# DBG-002.net
KiCad netlist of a schematic drawn in EAGLE
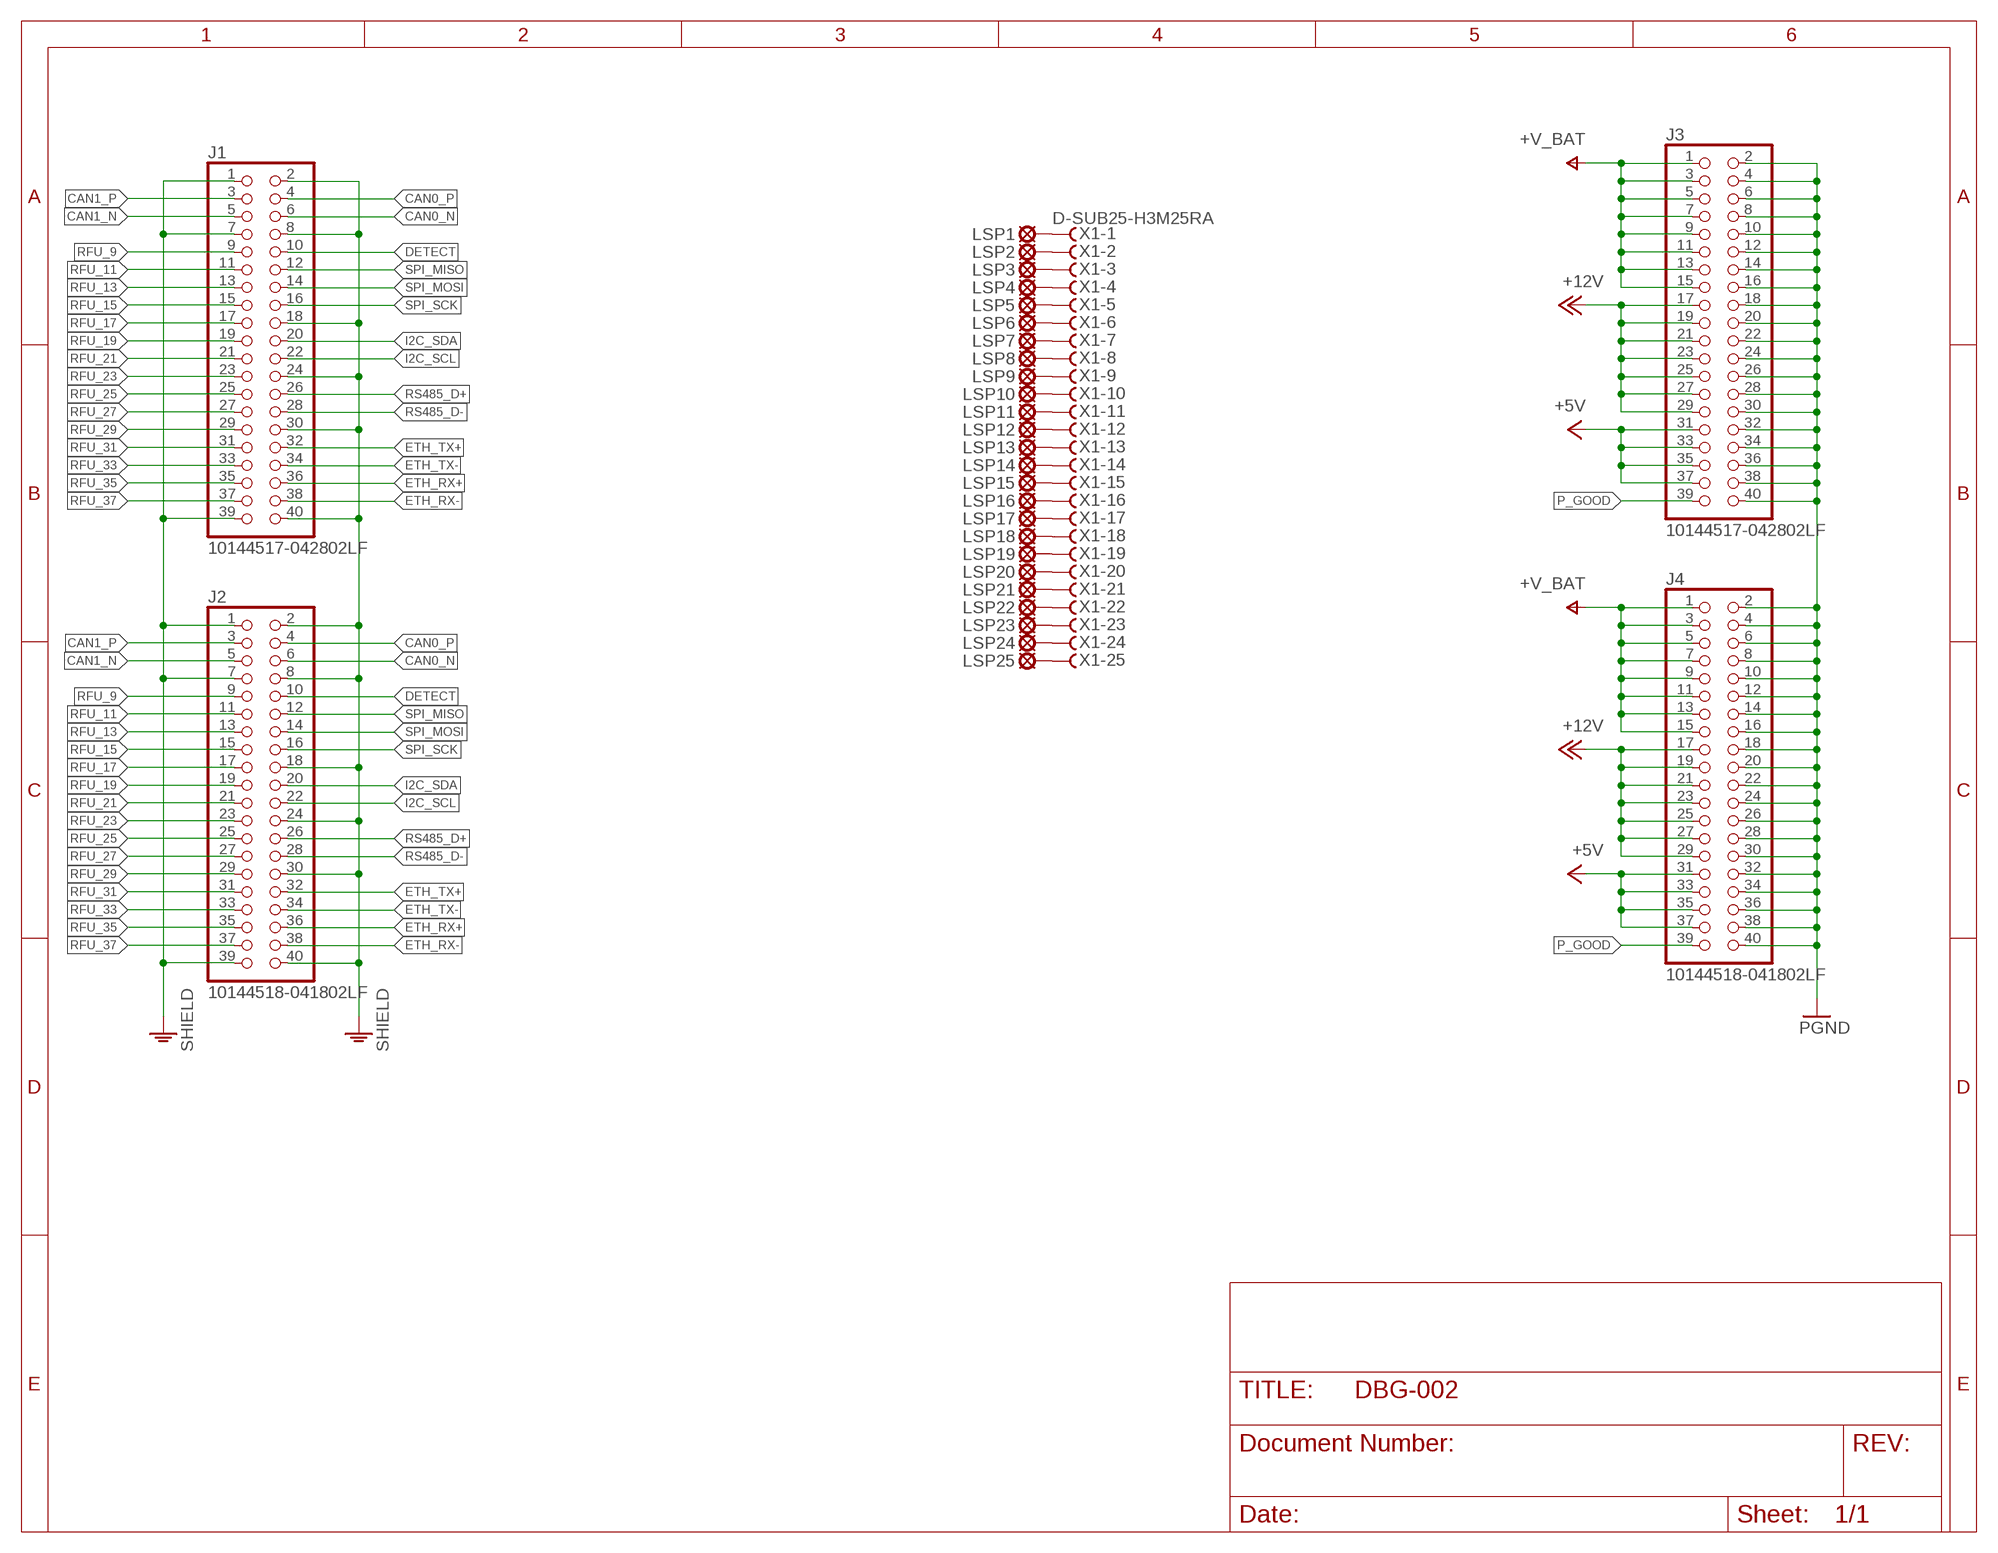
[diagram p0: schematic, sheet 1]

(export (version "E")
  (design (tool "Eeschema 10.0.6"))
  (components
    (comp (ref "J1")
      (value "10144517-042802LF")
      (footprint "eagle-import:10144517-042802LF")
      (libsource (lib "eagle-import") (part "10144517-042802LF"))
    )
    (comp (ref "J2")
      (value "10144518-041802LF")
      (footprint "eagle-import:10144518-041802LF")
      (libsource (lib "eagle-import") (part "10144518-041802LF"))
    )
    (comp (ref "J3")
      (value "10144517-042802LF")
      (footprint "eagle-import:10144517-042802LF")
      (libsource (lib "eagle-import") (part "10144517-042802LF"))
    )
    (comp (ref "J4")
      (value "10144518-041802LF")
      (footprint "eagle-import:10144518-041802LF")
      (libsource (lib "eagle-import") (part "10144518-041802LF"))
    )
    (comp (ref "LSP1")
      (value "LSP11")
      (footprint "eagle-import:LSP11")
      (libsource (lib "eagle-import") (part "LSP11"))
    )
    (comp (ref "LSP2")
      (value "LSP11")
      (footprint "eagle-import:LSP11")
      (libsource (lib "eagle-import") (part "LSP11"))
    )
    (comp (ref "LSP3")
      (value "LSP11")
      (footprint "eagle-import:LSP11")
      (libsource (lib "eagle-import") (part "LSP11"))
    )
    (comp (ref "LSP4")
      (value "LSP11")
      (footprint "eagle-import:LSP11")
      (libsource (lib "eagle-import") (part "LSP11"))
    )
    (comp (ref "LSP5")
      (value "LSP11")
      (footprint "eagle-import:LSP11")
      (libsource (lib "eagle-import") (part "LSP11"))
    )
    (comp (ref "LSP6")
      (value "LSP11")
      (footprint "eagle-import:LSP11")
      (libsource (lib "eagle-import") (part "LSP11"))
    )
    (comp (ref "LSP7")
      (value "LSP11")
      (footprint "eagle-import:LSP11")
      (libsource (lib "eagle-import") (part "LSP11"))
    )
    (comp (ref "LSP8")
      (value "LSP11")
      (footprint "eagle-import:LSP11")
      (libsource (lib "eagle-import") (part "LSP11"))
    )
    (comp (ref "LSP9")
      (value "LSP11")
      (footprint "eagle-import:LSP11")
      (libsource (lib "eagle-import") (part "LSP11"))
    )
    (comp (ref "LSP10")
      (value "LSP11")
      (footprint "eagle-import:LSP11")
      (libsource (lib "eagle-import") (part "LSP11"))
    )
    (comp (ref "LSP11")
      (value "LSP11")
      (footprint "eagle-import:LSP11")
      (libsource (lib "eagle-import") (part "LSP11"))
    )
    (comp (ref "LSP12")
      (value "LSP11")
      (footprint "eagle-import:LSP11")
      (libsource (lib "eagle-import") (part "LSP11"))
    )
    (comp (ref "LSP13")
      (value "LSP11")
      (footprint "eagle-import:LSP11")
      (libsource (lib "eagle-import") (part "LSP11"))
    )
    (comp (ref "LSP14")
      (value "LSP11")
      (footprint "eagle-import:LSP11")
      (libsource (lib "eagle-import") (part "LSP11"))
    )
    (comp (ref "LSP15")
      (value "LSP11")
      (footprint "eagle-import:LSP11")
      (libsource (lib "eagle-import") (part "LSP11"))
    )
    (comp (ref "LSP16")
      (value "LSP11")
      (footprint "eagle-import:LSP11")
      (libsource (lib "eagle-import") (part "LSP11"))
    )
    (comp (ref "LSP17")
      (value "LSP11")
      (footprint "eagle-import:LSP11")
      (libsource (lib "eagle-import") (part "LSP11"))
    )
    (comp (ref "LSP18")
      (value "LSP11")
      (footprint "eagle-import:LSP11")
      (libsource (lib "eagle-import") (part "LSP11"))
    )
    (comp (ref "LSP19")
      (value "LSP11")
      (footprint "eagle-import:LSP11")
      (libsource (lib "eagle-import") (part "LSP11"))
    )
    (comp (ref "LSP20")
      (value "LSP11")
      (footprint "eagle-import:LSP11")
      (libsource (lib "eagle-import") (part "LSP11"))
    )
    (comp (ref "LSP21")
      (value "LSP11")
      (footprint "eagle-import:LSP11")
      (libsource (lib "eagle-import") (part "LSP11"))
    )
    (comp (ref "LSP22")
      (value "LSP11")
      (footprint "eagle-import:LSP11")
      (libsource (lib "eagle-import") (part "LSP11"))
    )
    (comp (ref "LSP23")
      (value "LSP11")
      (footprint "eagle-import:LSP11")
      (libsource (lib "eagle-import") (part "LSP11"))
    )
    (comp (ref "LSP24")
      (value "LSP11")
      (footprint "eagle-import:LSP11")
      (libsource (lib "eagle-import") (part "LSP11"))
    )
    (comp (ref "LSP25")
      (value "LSP11")
      (footprint "eagle-import:LSP11")
      (libsource (lib "eagle-import") (part "LSP11"))
    )
    (comp (ref "X1")
      (value "D-SUB25-H3M25RA")
      (footprint "eagle-import:H3M25RA")
      (libsource (lib "eagle-import") (part "D-SUB25-H3M25RA"))
    )
  )
  (nets
    (net (code "1") (name "+5V") (class "Default")
      (node (ref "J3") (pin "31") (pinfunction "31_31") (pintype "passive"))
      (node (ref "J3") (pin "33") (pinfunction "33_33") (pintype "passive"))
      (node (ref "J3") (pin "35") (pinfunction "35_35") (pintype "passive"))
      (node (ref "J3") (pin "37") (pinfunction "37_37") (pintype "passive"))
      (node (ref "J4") (pin "31") (pinfunction "31_31") (pintype "passive"))
      (node (ref "J4") (pin "33") (pinfunction "33_33") (pintype "passive"))
      (node (ref "J4") (pin "35") (pinfunction "35_35") (pintype "passive"))
      (node (ref "J4") (pin "37") (pinfunction "37_37") (pintype "passive"))
    )
    (net (code "2") (name "+12V") (class "Default")
      (node (ref "J3") (pin "17") (pinfunction "17_17") (pintype "passive"))
      (node (ref "J3") (pin "19") (pinfunction "19_19") (pintype "passive"))
      (node (ref "J3") (pin "21") (pinfunction "21_21") (pintype "passive"))
      (node (ref "J3") (pin "23") (pinfunction "23_23") (pintype "passive"))
      (node (ref "J3") (pin "25") (pinfunction "25_25") (pintype "passive"))
      (node (ref "J3") (pin "27") (pinfunction "27_27") (pintype "passive"))
      (node (ref "J3") (pin "29") (pinfunction "29_29") (pintype "passive"))
      (node (ref "J4") (pin "17") (pinfunction "17_17") (pintype "passive"))
      (node (ref "J4") (pin "19") (pinfunction "19_19") (pintype "passive"))
      (node (ref "J4") (pin "21") (pinfunction "21_21") (pintype "passive"))
      (node (ref "J4") (pin "23") (pinfunction "23_23") (pintype "passive"))
      (node (ref "J4") (pin "25") (pinfunction "25_25") (pintype "passive"))
      (node (ref "J4") (pin "27") (pinfunction "27_27") (pintype "passive"))
      (node (ref "J4") (pin "29") (pinfunction "29_29") (pintype "passive"))
    )
    (net (code "3") (name "+V_BAT") (class "Default")
      (node (ref "J3") (pin "1") (pinfunction "1_1") (pintype "passive"))
      (node (ref "J3") (pin "11") (pinfunction "11_11") (pintype "passive"))
      (node (ref "J3") (pin "13") (pinfunction "13_13") (pintype "passive"))
      (node (ref "J3") (pin "15") (pinfunction "15_15") (pintype "passive"))
      (node (ref "J3") (pin "3") (pinfunction "3_3") (pintype "passive"))
      (node (ref "J3") (pin "5") (pinfunction "5_5") (pintype "passive"))
      (node (ref "J3") (pin "7") (pinfunction "7_7") (pintype "passive"))
      (node (ref "J3") (pin "9") (pinfunction "9_9") (pintype "passive"))
      (node (ref "J4") (pin "1") (pinfunction "1_1") (pintype "passive"))
      (node (ref "J4") (pin "11") (pinfunction "11_11") (pintype "passive"))
      (node (ref "J4") (pin "13") (pinfunction "13_13") (pintype "passive"))
      (node (ref "J4") (pin "15") (pinfunction "15_15") (pintype "passive"))
      (node (ref "J4") (pin "3") (pinfunction "3_3") (pintype "passive"))
      (node (ref "J4") (pin "5") (pinfunction "5_5") (pintype "passive"))
      (node (ref "J4") (pin "7") (pinfunction "7_7") (pintype "passive"))
      (node (ref "J4") (pin "9") (pinfunction "9_9") (pintype "passive"))
    )
    (net (code "4") (name "CAN0_N") (class "Default")
      (node (ref "J1") (pin "6") (pinfunction "6_6") (pintype "passive"))
      (node (ref "J2") (pin "6") (pinfunction "6_6") (pintype "passive"))
    )
    (net (code "5") (name "CAN0_P") (class "Default")
      (node (ref "J1") (pin "4") (pinfunction "4_4") (pintype "passive"))
      (node (ref "J2") (pin "4") (pinfunction "4_4") (pintype "passive"))
    )
    (net (code "6") (name "CAN1_N") (class "Default")
      (node (ref "J1") (pin "5") (pinfunction "5_5") (pintype "passive"))
      (node (ref "J2") (pin "5") (pinfunction "5_5") (pintype "passive"))
    )
    (net (code "7") (name "CAN1_P") (class "Default")
      (node (ref "J1") (pin "3") (pinfunction "3_3") (pintype "passive"))
      (node (ref "J2") (pin "3") (pinfunction "3_3") (pintype "passive"))
    )
    (net (code "8") (name "DETECT") (class "Default")
      (node (ref "J1") (pin "10") (pinfunction "10_10") (pintype "passive"))
      (node (ref "J2") (pin "10") (pinfunction "10_10") (pintype "passive"))
    )
    (net (code "9") (name "ETH_RX+") (class "Default")
      (node (ref "J1") (pin "36") (pinfunction "36_36") (pintype "passive"))
      (node (ref "J2") (pin "36") (pinfunction "36_36") (pintype "passive"))
    )
    (net (code "10") (name "ETH_RX-") (class "Default")
      (node (ref "J1") (pin "38") (pinfunction "38_38") (pintype "passive"))
      (node (ref "J2") (pin "38") (pinfunction "38_38") (pintype "passive"))
    )
    (net (code "11") (name "ETH_TX+") (class "Default")
      (node (ref "J1") (pin "32") (pinfunction "32_32") (pintype "passive"))
      (node (ref "J2") (pin "32") (pinfunction "32_32") (pintype "passive"))
    )
    (net (code "12") (name "ETH_TX-") (class "Default")
      (node (ref "J1") (pin "34") (pinfunction "34_34") (pintype "passive"))
      (node (ref "J2") (pin "34") (pinfunction "34_34") (pintype "passive"))
    )
    (net (code "13") (name "I2C_SCL") (class "Default")
      (node (ref "J1") (pin "22") (pinfunction "22_22") (pintype "passive"))
      (node (ref "J2") (pin "22") (pinfunction "22_22") (pintype "passive"))
    )
    (net (code "14") (name "I2C_SDA") (class "Default")
      (node (ref "J1") (pin "20") (pinfunction "20_20") (pintype "passive"))
      (node (ref "J2") (pin "20") (pinfunction "20_20") (pintype "passive"))
    )
    (net (code "15") (name "Net-(X1A-F)") (class "Default")
      (node (ref "LSP1") (pin "MP") (pinfunction "MP_MP") (pintype "passive"))
      (node (ref "X1") (pin "1") (pinfunction "F_1") (pintype "passive"))
    )
    (net (code "16") (name "Net-(X1B-F)") (class "Default")
      (node (ref "LSP10") (pin "MP") (pinfunction "MP_MP") (pintype "passive"))
      (node (ref "X1") (pin "10") (pinfunction "F_10") (pintype "passive"))
    )
    (net (code "17") (name "Net-(X1C-F)") (class "Default")
      (node (ref "LSP11") (pin "MP") (pinfunction "MP_MP") (pintype "passive"))
      (node (ref "X1") (pin "11") (pinfunction "F_11") (pintype "passive"))
    )
    (net (code "18") (name "Net-(X1D-F)") (class "Default")
      (node (ref "LSP12") (pin "MP") (pinfunction "MP_MP") (pintype "passive"))
      (node (ref "X1") (pin "12") (pinfunction "F_12") (pintype "passive"))
    )
    (net (code "19") (name "Net-(X1E-F)") (class "Default")
      (node (ref "LSP13") (pin "MP") (pinfunction "MP_MP") (pintype "passive"))
      (node (ref "X1") (pin "13") (pinfunction "F_13") (pintype "passive"))
    )
    (net (code "20") (name "Net-(X1F-F)") (class "Default")
      (node (ref "LSP14") (pin "MP") (pinfunction "MP_MP") (pintype "passive"))
      (node (ref "X1") (pin "14") (pinfunction "F_14") (pintype "passive"))
    )
    (net (code "21") (name "Net-(X1G-F)") (class "Default")
      (node (ref "LSP15") (pin "MP") (pinfunction "MP_MP") (pintype "passive"))
      (node (ref "X1") (pin "15") (pinfunction "F_15") (pintype "passive"))
    )
    (net (code "22") (name "Net-(X1H-F)") (class "Default")
      (node (ref "LSP16") (pin "MP") (pinfunction "MP_MP") (pintype "passive"))
      (node (ref "X1") (pin "16") (pinfunction "F_16") (pintype "passive"))
    )
    (net (code "23") (name "Net-(X1I-F)") (class "Default")
      (node (ref "LSP17") (pin "MP") (pinfunction "MP_MP") (pintype "passive"))
      (node (ref "X1") (pin "17") (pinfunction "F_17") (pintype "passive"))
    )
    (net (code "24") (name "Net-(X1J-F)") (class "Default")
      (node (ref "LSP18") (pin "MP") (pinfunction "MP_MP") (pintype "passive"))
      (node (ref "X1") (pin "18") (pinfunction "F_18") (pintype "passive"))
    )
    (net (code "25") (name "Net-(X1K-F)") (class "Default")
      (node (ref "LSP19") (pin "MP") (pinfunction "MP_MP") (pintype "passive"))
      (node (ref "X1") (pin "19") (pinfunction "F_19") (pintype "passive"))
    )
    (net (code "26") (name "Net-(X1L-F)") (class "Default")
      (node (ref "LSP2") (pin "MP") (pinfunction "MP_MP") (pintype "passive"))
      (node (ref "X1") (pin "2") (pinfunction "F_2") (pintype "passive"))
    )
    (net (code "27") (name "Net-(X1M-F)") (class "Default")
      (node (ref "LSP20") (pin "MP") (pinfunction "MP_MP") (pintype "passive"))
      (node (ref "X1") (pin "20") (pinfunction "F_20") (pintype "passive"))
    )
    (net (code "28") (name "Net-(X1N-F)") (class "Default")
      (node (ref "LSP21") (pin "MP") (pinfunction "MP_MP") (pintype "passive"))
      (node (ref "X1") (pin "21") (pinfunction "F_21") (pintype "passive"))
    )
    (net (code "29") (name "Net-(X1O-F)") (class "Default")
      (node (ref "LSP22") (pin "MP") (pinfunction "MP_MP") (pintype "passive"))
      (node (ref "X1") (pin "22") (pinfunction "F_22") (pintype "passive"))
    )
    (net (code "30") (name "Net-(X1P-F)") (class "Default")
      (node (ref "LSP23") (pin "MP") (pinfunction "MP_MP") (pintype "passive"))
      (node (ref "X1") (pin "23") (pinfunction "F_23") (pintype "passive"))
    )
    (net (code "31") (name "Net-(X1Q-F)") (class "Default")
      (node (ref "LSP24") (pin "MP") (pinfunction "MP_MP") (pintype "passive"))
      (node (ref "X1") (pin "24") (pinfunction "F_24") (pintype "passive"))
    )
    (net (code "32") (name "Net-(X1R-F)") (class "Default")
      (node (ref "LSP25") (pin "MP") (pinfunction "MP_MP") (pintype "passive"))
      (node (ref "X1") (pin "25") (pinfunction "F_25") (pintype "passive"))
    )
    (net (code "33") (name "Net-(X1S-F)") (class "Default")
      (node (ref "LSP3") (pin "MP") (pinfunction "MP_MP") (pintype "passive"))
      (node (ref "X1") (pin "3") (pinfunction "F_3") (pintype "passive"))
    )
    (net (code "34") (name "Net-(X1T-F)") (class "Default")
      (node (ref "LSP4") (pin "MP") (pinfunction "MP_MP") (pintype "passive"))
      (node (ref "X1") (pin "4") (pinfunction "F_4") (pintype "passive"))
    )
    (net (code "35") (name "Net-(X1U-F)") (class "Default")
      (node (ref "LSP5") (pin "MP") (pinfunction "MP_MP") (pintype "passive"))
      (node (ref "X1") (pin "5") (pinfunction "F_5") (pintype "passive"))
    )
    (net (code "36") (name "Net-(X1V-F)") (class "Default")
      (node (ref "LSP6") (pin "MP") (pinfunction "MP_MP") (pintype "passive"))
      (node (ref "X1") (pin "6") (pinfunction "F_6") (pintype "passive"))
    )
    (net (code "37") (name "Net-(X1W-F)") (class "Default")
      (node (ref "LSP7") (pin "MP") (pinfunction "MP_MP") (pintype "passive"))
      (node (ref "X1") (pin "7") (pinfunction "F_7") (pintype "passive"))
    )
    (net (code "38") (name "Net-(X1X-F)") (class "Default")
      (node (ref "LSP8") (pin "MP") (pinfunction "MP_MP") (pintype "passive"))
      (node (ref "X1") (pin "8") (pinfunction "F_8") (pintype "passive"))
    )
    (net (code "39") (name "Net-(X1Y-F)") (class "Default")
      (node (ref "LSP9") (pin "MP") (pinfunction "MP_MP") (pintype "passive"))
      (node (ref "X1") (pin "9") (pinfunction "F_9") (pintype "passive"))
    )
    (net (code "40") (name "PGND") (class "Default")
      (node (ref "J3") (pin "10") (pinfunction "10_10") (pintype "passive"))
      (node (ref "J3") (pin "12") (pinfunction "12_12") (pintype "passive"))
      (node (ref "J3") (pin "14") (pinfunction "14_14") (pintype "passive"))
      (node (ref "J3") (pin "16") (pinfunction "16_16") (pintype "passive"))
      (node (ref "J3") (pin "18") (pinfunction "18_18") (pintype "passive"))
      (node (ref "J3") (pin "2") (pinfunction "2_2") (pintype "passive"))
      (node (ref "J3") (pin "20") (pinfunction "20_20") (pintype "passive"))
      (node (ref "J3") (pin "22") (pinfunction "22_22") (pintype "passive"))
      (node (ref "J3") (pin "24") (pinfunction "24_24") (pintype "passive"))
      (node (ref "J3") (pin "26") (pinfunction "26_26") (pintype "passive"))
      (node (ref "J3") (pin "28") (pinfunction "28_28") (pintype "passive"))
      (node (ref "J3") (pin "30") (pinfunction "30_30") (pintype "passive"))
      (node (ref "J3") (pin "32") (pinfunction "32_32") (pintype "passive"))
      (node (ref "J3") (pin "34") (pinfunction "34_34") (pintype "passive"))
      (node (ref "J3") (pin "36") (pinfunction "36_36") (pintype "passive"))
      (node (ref "J3") (pin "38") (pinfunction "38_38") (pintype "passive"))
      (node (ref "J3") (pin "4") (pinfunction "4_4") (pintype "passive"))
      (node (ref "J3") (pin "40") (pinfunction "40_40") (pintype "passive"))
      (node (ref "J3") (pin "6") (pinfunction "6_6") (pintype "passive"))
      (node (ref "J3") (pin "8") (pinfunction "8_8") (pintype "passive"))
      (node (ref "J4") (pin "10") (pinfunction "10_10") (pintype "passive"))
      (node (ref "J4") (pin "12") (pinfunction "12_12") (pintype "passive"))
      (node (ref "J4") (pin "14") (pinfunction "14_14") (pintype "passive"))
      (node (ref "J4") (pin "16") (pinfunction "16_16") (pintype "passive"))
      (node (ref "J4") (pin "18") (pinfunction "18_18") (pintype "passive"))
      (node (ref "J4") (pin "2") (pinfunction "2_2") (pintype "passive"))
      (node (ref "J4") (pin "20") (pinfunction "20_20") (pintype "passive"))
      (node (ref "J4") (pin "22") (pinfunction "22_22") (pintype "passive"))
      (node (ref "J4") (pin "24") (pinfunction "24_24") (pintype "passive"))
      (node (ref "J4") (pin "26") (pinfunction "26_26") (pintype "passive"))
      (node (ref "J4") (pin "28") (pinfunction "28_28") (pintype "passive"))
      (node (ref "J4") (pin "30") (pinfunction "30_30") (pintype "passive"))
      (node (ref "J4") (pin "32") (pinfunction "32_32") (pintype "passive"))
      (node (ref "J4") (pin "34") (pinfunction "34_34") (pintype "passive"))
      (node (ref "J4") (pin "36") (pinfunction "36_36") (pintype "passive"))
      (node (ref "J4") (pin "38") (pinfunction "38_38") (pintype "passive"))
      (node (ref "J4") (pin "4") (pinfunction "4_4") (pintype "passive"))
      (node (ref "J4") (pin "40") (pinfunction "40_40") (pintype "passive"))
      (node (ref "J4") (pin "6") (pinfunction "6_6") (pintype "passive"))
      (node (ref "J4") (pin "8") (pinfunction "8_8") (pintype "passive"))
    )
    (net (code "41") (name "P_GOOD") (class "Default")
      (node (ref "J3") (pin "39") (pinfunction "39_39") (pintype "passive"))
      (node (ref "J4") (pin "39") (pinfunction "39_39") (pintype "passive"))
    )
    (net (code "42") (name "RFU_9") (class "Default")
      (node (ref "J1") (pin "9") (pinfunction "9_9") (pintype "passive"))
      (node (ref "J2") (pin "9") (pinfunction "9_9") (pintype "passive"))
    )
    (net (code "43") (name "RFU_11") (class "Default")
      (node (ref "J1") (pin "11") (pinfunction "11_11") (pintype "passive"))
      (node (ref "J2") (pin "11") (pinfunction "11_11") (pintype "passive"))
    )
    (net (code "44") (name "RFU_13") (class "Default")
      (node (ref "J1") (pin "13") (pinfunction "13_13") (pintype "passive"))
      (node (ref "J2") (pin "13") (pinfunction "13_13") (pintype "passive"))
    )
    (net (code "45") (name "RFU_15") (class "Default")
      (node (ref "J1") (pin "15") (pinfunction "15_15") (pintype "passive"))
      (node (ref "J2") (pin "15") (pinfunction "15_15") (pintype "passive"))
    )
    (net (code "46") (name "RFU_17") (class "Default")
      (node (ref "J1") (pin "17") (pinfunction "17_17") (pintype "passive"))
      (node (ref "J2") (pin "17") (pinfunction "17_17") (pintype "passive"))
    )
    (net (code "47") (name "RFU_19") (class "Default")
      (node (ref "J1") (pin "19") (pinfunction "19_19") (pintype "passive"))
      (node (ref "J2") (pin "19") (pinfunction "19_19") (pintype "passive"))
    )
    (net (code "48") (name "RFU_21") (class "Default")
      (node (ref "J1") (pin "21") (pinfunction "21_21") (pintype "passive"))
      (node (ref "J2") (pin "21") (pinfunction "21_21") (pintype "passive"))
    )
    (net (code "49") (name "RFU_23") (class "Default")
      (node (ref "J1") (pin "23") (pinfunction "23_23") (pintype "passive"))
      (node (ref "J2") (pin "23") (pinfunction "23_23") (pintype "passive"))
    )
    (net (code "50") (name "RFU_25") (class "Default")
      (node (ref "J1") (pin "25") (pinfunction "25_25") (pintype "passive"))
      (node (ref "J2") (pin "25") (pinfunction "25_25") (pintype "passive"))
    )
    (net (code "51") (name "RFU_27") (class "Default")
      (node (ref "J1") (pin "27") (pinfunction "27_27") (pintype "passive"))
      (node (ref "J2") (pin "27") (pinfunction "27_27") (pintype "passive"))
    )
    (net (code "52") (name "RFU_29") (class "Default")
      (node (ref "J1") (pin "29") (pinfunction "29_29") (pintype "passive"))
      (node (ref "J2") (pin "29") (pinfunction "29_29") (pintype "passive"))
    )
    (net (code "53") (name "RFU_31") (class "Default")
      (node (ref "J1") (pin "31") (pinfunction "31_31") (pintype "passive"))
      (node (ref "J2") (pin "31") (pinfunction "31_31") (pintype "passive"))
    )
    (net (code "54") (name "RFU_33") (class "Default")
      (node (ref "J1") (pin "33") (pinfunction "33_33") (pintype "passive"))
      (node (ref "J2") (pin "33") (pinfunction "33_33") (pintype "passive"))
    )
    (net (code "55") (name "RFU_35") (class "Default")
      (node (ref "J1") (pin "35") (pinfunction "35_35") (pintype "passive"))
      (node (ref "J2") (pin "35") (pinfunction "35_35") (pintype "passive"))
    )
    (net (code "56") (name "RFU_37") (class "Default")
      (node (ref "J1") (pin "37") (pinfunction "37_37") (pintype "passive"))
      (node (ref "J2") (pin "37") (pinfunction "37_37") (pintype "passive"))
    )
    (net (code "57") (name "RS485_D+") (class "Default")
      (node (ref "J1") (pin "26") (pinfunction "26_26") (pintype "passive"))
      (node (ref "J2") (pin "26") (pinfunction "26_26") (pintype "passive"))
    )
    (net (code "58") (name "RS485_D-") (class "Default")
      (node (ref "J1") (pin "28") (pinfunction "28_28") (pintype "passive"))
      (node (ref "J2") (pin "28") (pinfunction "28_28") (pintype "passive"))
    )
    (net (code "59") (name "SHIELD") (class "Default")
      (node (ref "J1") (pin "1") (pinfunction "1_1") (pintype "passive"))
      (node (ref "J1") (pin "18") (pinfunction "18_18") (pintype "passive"))
      (node (ref "J1") (pin "2") (pinfunction "2_2") (pintype "passive"))
      (node (ref "J1") (pin "24") (pinfunction "24_24") (pintype "passive"))
      (node (ref "J1") (pin "30") (pinfunction "30_30") (pintype "passive"))
      (node (ref "J1") (pin "39") (pinfunction "39_39") (pintype "passive"))
      (node (ref "J1") (pin "40") (pinfunction "40_40") (pintype "passive"))
      (node (ref "J1") (pin "7") (pinfunction "7_7") (pintype "passive"))
      (node (ref "J1") (pin "8") (pinfunction "8_8") (pintype "passive"))
      (node (ref "J2") (pin "1") (pinfunction "1_1") (pintype "passive"))
      (node (ref "J2") (pin "18") (pinfunction "18_18") (pintype "passive"))
      (node (ref "J2") (pin "2") (pinfunction "2_2") (pintype "passive"))
      (node (ref "J2") (pin "24") (pinfunction "24_24") (pintype "passive"))
      (node (ref "J2") (pin "30") (pinfunction "30_30") (pintype "passive"))
      (node (ref "J2") (pin "39") (pinfunction "39_39") (pintype "passive"))
      (node (ref "J2") (pin "40") (pinfunction "40_40") (pintype "passive"))
      (node (ref "J2") (pin "7") (pinfunction "7_7") (pintype "passive"))
      (node (ref "J2") (pin "8") (pinfunction "8_8") (pintype "passive"))
    )
    (net (code "60") (name "SPI_MISO") (class "Default")
      (node (ref "J1") (pin "12") (pinfunction "12_12") (pintype "passive"))
      (node (ref "J2") (pin "12") (pinfunction "12_12") (pintype "passive"))
    )
    (net (code "61") (name "SPI_MOSI") (class "Default")
      (node (ref "J1") (pin "14") (pinfunction "14_14") (pintype "passive"))
      (node (ref "J2") (pin "14") (pinfunction "14_14") (pintype "passive"))
    )
    (net (code "62") (name "SPI_SCK") (class "Default")
      (node (ref "J1") (pin "16") (pinfunction "16_16") (pintype "passive"))
      (node (ref "J2") (pin "16") (pinfunction "16_16") (pintype "passive"))
    )
  )
)
